# Central_Unit_PCB.net
KiCad netlist of a schematic drawn in EAGLE
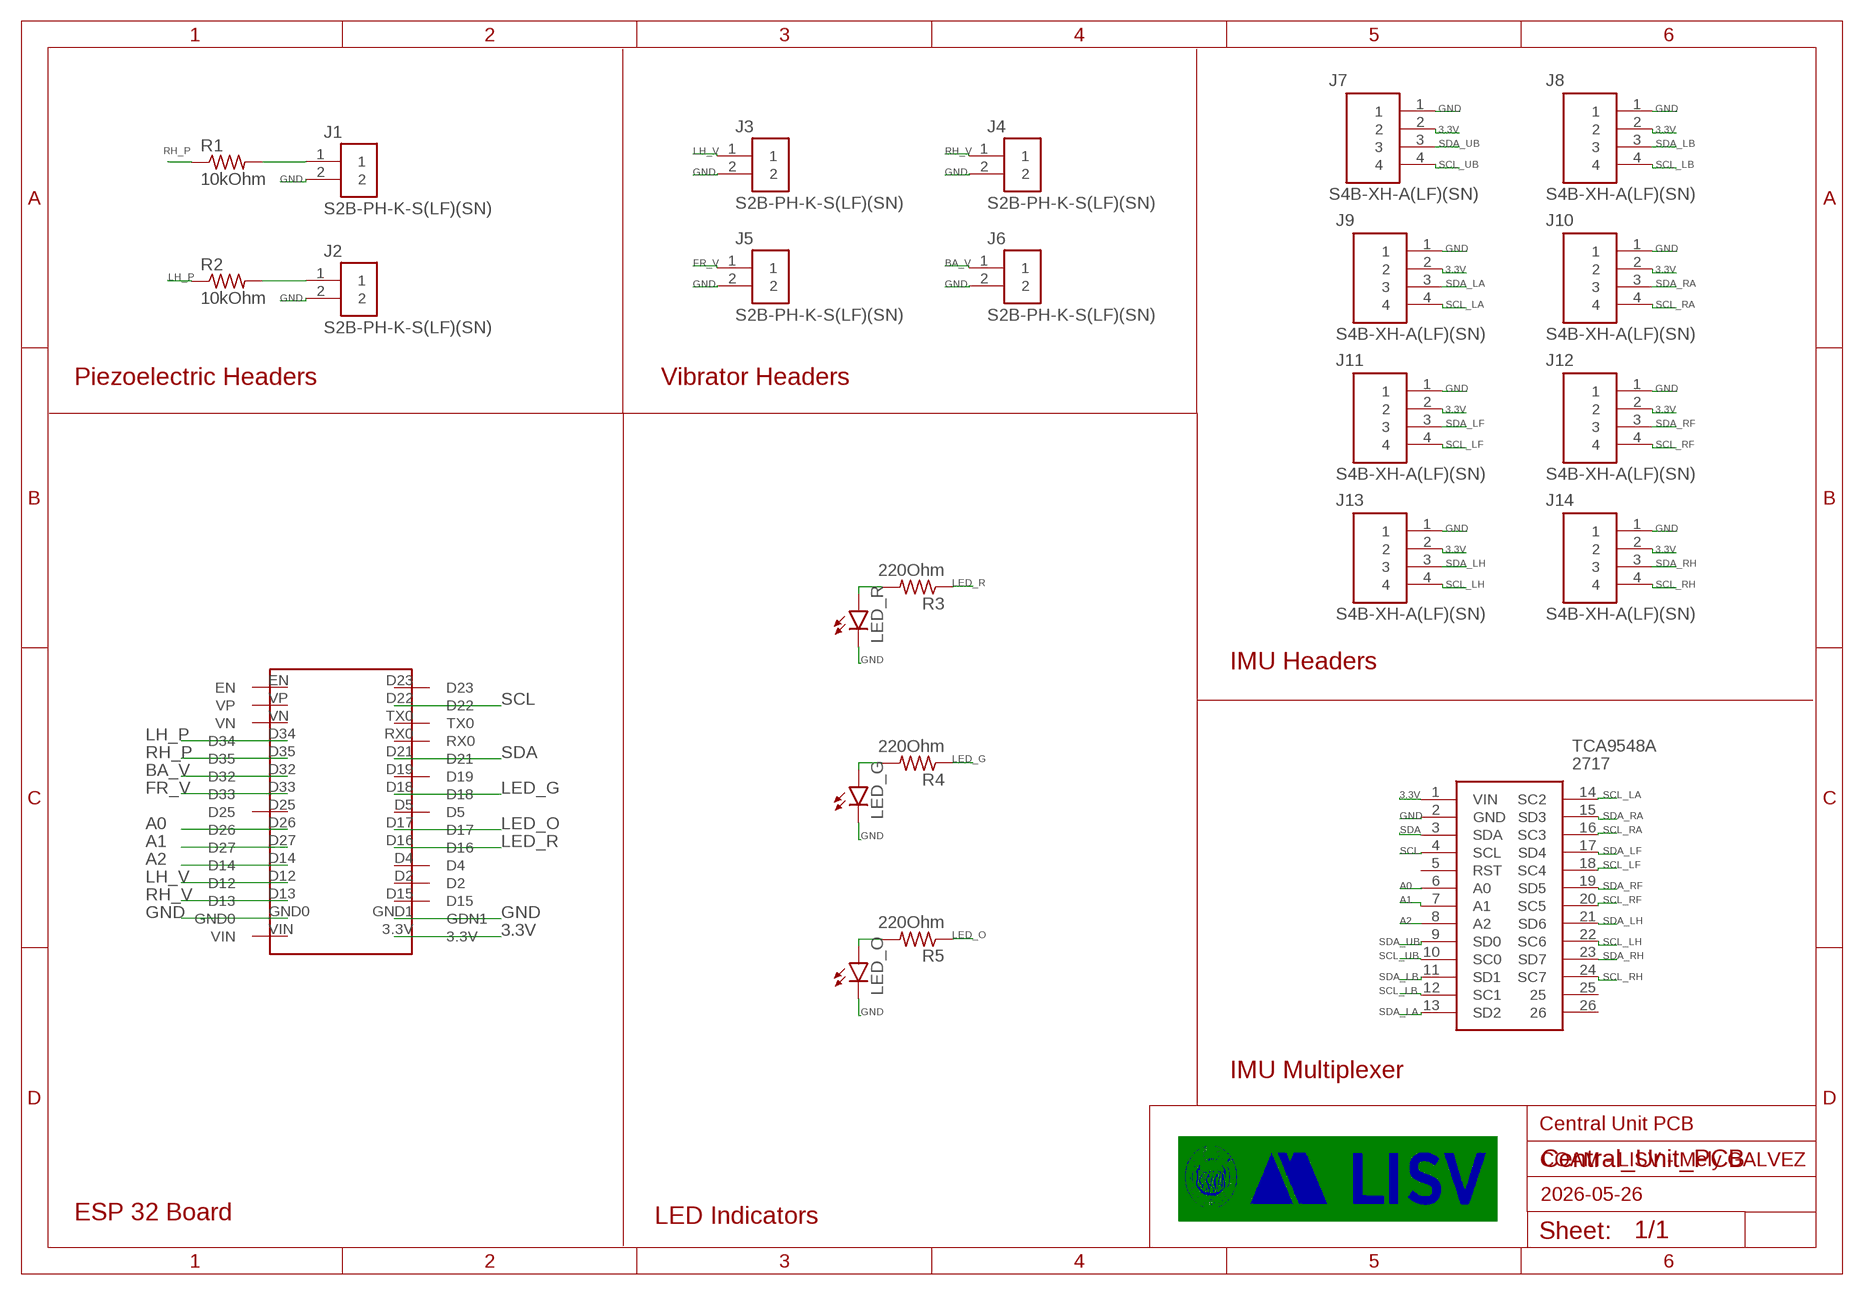
[diagram p0: schematic, sheet 1]

(export (version "E")
  (design (tool "Eeschema 10.0.6"))
  (components
    (comp (ref "J1")
      (value "S2B-PH-K-S(LF)(SN)")
      (footprint "eagle-import:S2B-PH-K-S(LF)(SN)")
      (fields
        (field (name "DIGI_KEY_PART_NUMBER") "455-1719-ND")
        (field (name "MANUFACTURER") "JST Sales America Inc.")
        (field (name "CREATED_BY") "PCBLayout.com")
      )
      (libsource (lib "eagle-import") (part "S2B-PH-K-S(LF)(SN)"))
    )
    (comp (ref "J2")
      (value "S2B-PH-K-S(LF)(SN)")
      (footprint "eagle-import:S2B-PH-K-S(LF)(SN)")
      (fields
        (field (name "DIGI_KEY_PART_NUMBER") "455-1719-ND")
        (field (name "MANUFACTURER") "JST Sales America Inc.")
        (field (name "CREATED_BY") "PCBLayout.com")
      )
      (libsource (lib "eagle-import") (part "S2B-PH-K-S(LF)(SN)"))
    )
    (comp (ref "J3")
      (value "S2B-PH-K-S(LF)(SN)")
      (footprint "eagle-import:S2B-PH-K-S(LF)(SN)")
      (fields
        (field (name "DIGI_KEY_PART_NUMBER") "455-1719-ND")
        (field (name "MANUFACTURER") "JST Sales America Inc.")
        (field (name "CREATED_BY") "PCBLayout.com")
      )
      (libsource (lib "eagle-import") (part "S2B-PH-K-S(LF)(SN)"))
    )
    (comp (ref "J4")
      (value "S2B-PH-K-S(LF)(SN)")
      (footprint "eagle-import:S2B-PH-K-S(LF)(SN)")
      (fields
        (field (name "DIGI_KEY_PART_NUMBER") "455-1719-ND")
        (field (name "MANUFACTURER") "JST Sales America Inc.")
        (field (name "CREATED_BY") "PCBLayout.com")
      )
      (libsource (lib "eagle-import") (part "S2B-PH-K-S(LF)(SN)"))
    )
    (comp (ref "J5")
      (value "S2B-PH-K-S(LF)(SN)")
      (footprint "eagle-import:S2B-PH-K-S(LF)(SN)")
      (fields
        (field (name "DIGI_KEY_PART_NUMBER") "455-1719-ND")
        (field (name "MANUFACTURER") "JST Sales America Inc.")
        (field (name "CREATED_BY") "PCBLayout.com")
      )
      (libsource (lib "eagle-import") (part "S2B-PH-K-S(LF)(SN)"))
    )
    (comp (ref "J6")
      (value "S2B-PH-K-S(LF)(SN)")
      (footprint "eagle-import:S2B-PH-K-S(LF)(SN)")
      (fields
        (field (name "DIGI_KEY_PART_NUMBER") "455-1719-ND")
        (field (name "MANUFACTURER") "JST Sales America Inc.")
        (field (name "CREATED_BY") "PCBLayout.com")
      )
      (libsource (lib "eagle-import") (part "S2B-PH-K-S(LF)(SN)"))
    )
    (comp (ref "J7")
      (value "S4B-XH-A(LF)(SN)")
      (footprint "eagle-import:HDR-04_RA")
      (fields
        (field (name "DIGIKEY_PART_NUMBER") "455-2243-ND")
        (field (name "MANUFACTURER") "JST Sales America Inc.")
        (field (name "CREATED_BY") "PCBLayout.com")
      )
      (libsource (lib "eagle-import") (part "S4B-XH-A(LF)(SN)"))
    )
    (comp (ref "J8")
      (value "S4B-XH-A(LF)(SN)")
      (footprint "eagle-import:HDR-04_RA")
      (fields
        (field (name "DIGIKEY_PART_NUMBER") "455-2243-ND")
        (field (name "MANUFACTURER") "JST Sales America Inc.")
        (field (name "CREATED_BY") "PCBLayout.com")
      )
      (libsource (lib "eagle-import") (part "S4B-XH-A(LF)(SN)"))
    )
    (comp (ref "J9")
      (value "S4B-XH-A(LF)(SN)")
      (footprint "eagle-import:HDR-04_RA")
      (fields
        (field (name "DIGIKEY_PART_NUMBER") "455-2243-ND")
        (field (name "MANUFACTURER") "JST Sales America Inc.")
        (field (name "CREATED_BY") "PCBLayout.com")
      )
      (libsource (lib "eagle-import") (part "S4B-XH-A(LF)(SN)"))
    )
    (comp (ref "J10")
      (value "S4B-XH-A(LF)(SN)")
      (footprint "eagle-import:HDR-04_RA")
      (fields
        (field (name "DIGIKEY_PART_NUMBER") "455-2243-ND")
        (field (name "MANUFACTURER") "JST Sales America Inc.")
        (field (name "CREATED_BY") "PCBLayout.com")
      )
      (libsource (lib "eagle-import") (part "S4B-XH-A(LF)(SN)"))
    )
    (comp (ref "J11")
      (value "S4B-XH-A(LF)(SN)")
      (footprint "eagle-import:HDR-04_RA")
      (fields
        (field (name "DIGIKEY_PART_NUMBER") "455-2243-ND")
        (field (name "MANUFACTURER") "JST Sales America Inc.")
        (field (name "CREATED_BY") "PCBLayout.com")
      )
      (libsource (lib "eagle-import") (part "S4B-XH-A(LF)(SN)"))
    )
    (comp (ref "J12")
      (value "S4B-XH-A(LF)(SN)")
      (footprint "eagle-import:HDR-04_RA")
      (fields
        (field (name "DIGIKEY_PART_NUMBER") "455-2243-ND")
        (field (name "MANUFACTURER") "JST Sales America Inc.")
        (field (name "CREATED_BY") "PCBLayout.com")
      )
      (libsource (lib "eagle-import") (part "S4B-XH-A(LF)(SN)"))
    )
    (comp (ref "J13")
      (value "S4B-XH-A(LF)(SN)")
      (footprint "eagle-import:HDR-04_RA")
      (fields
        (field (name "DIGIKEY_PART_NUMBER") "455-2243-ND")
        (field (name "MANUFACTURER") "JST Sales America Inc.")
        (field (name "CREATED_BY") "PCBLayout.com")
      )
      (libsource (lib "eagle-import") (part "S4B-XH-A(LF)(SN)"))
    )
    (comp (ref "J14")
      (value "S4B-XH-A(LF)(SN)")
      (footprint "eagle-import:HDR-04_RA")
      (fields
        (field (name "DIGIKEY_PART_NUMBER") "455-2243-ND")
        (field (name "MANUFACTURER") "JST Sales America Inc.")
        (field (name "CREATED_BY") "PCBLayout.com")
      )
      (libsource (lib "eagle-import") (part "S4B-XH-A(LF)(SN)"))
    )
    (comp (ref "LED_G")
      (value "LED3MM")
      (footprint "eagle-import:LED3MM")
      (libsource (lib "eagle-import") (part "LED3MM"))
    )
    (comp (ref "LED_O")
      (value "LED3MM")
      (footprint "eagle-import:LED3MM")
      (libsource (lib "eagle-import") (part "LED3MM"))
    )
    (comp (ref "LED_R")
      (value "LED3MM")
      (footprint "eagle-import:LED3MM")
      (libsource (lib "eagle-import") (part "LED3MM"))
    )
    (comp (ref "R1")
      (value "10kOhm")
      (footprint "eagle-import:0207_10")
      (libsource (lib "eagle-import") (part "R-US_0207/10"))
    )
    (comp (ref "R2")
      (value "10kOhm")
      (footprint "eagle-import:0207_10")
      (libsource (lib "eagle-import") (part "R-US_0207/10"))
    )
    (comp (ref "R3")
      (value "220Ohm")
      (footprint "eagle-import:0207_10")
      (libsource (lib "eagle-import") (part "R-US_0207/10"))
    )
    (comp (ref "R4")
      (value "220Ohm")
      (footprint "eagle-import:0207_10")
      (libsource (lib "eagle-import") (part "R-US_0207/10"))
    )
    (comp (ref "R5")
      (value "220Ohm")
      (footprint "eagle-import:0207_10")
      (libsource (lib "eagle-import") (part "R-US_0207/10"))
    )
    (comp (ref "TCA9548A")
      (value "2717")
      (footprint "eagle-import:2717")
      (fields (field (name "MOUSER_PART_NUMBER") "485-2717"))
      (libsource (lib "eagle-import") (part "2717"))
    )
    (comp (ref "U$1")
      (value "ESP32_WROUM32")
      (footprint "eagle-import:ESP32_WROUM32")
      (libsource (lib "eagle-import") (part "ESP32_WROUM32"))
    )
  )
  (nets
    (net (code "1") (name "/3.3V") (class "Default")
      (node (ref "J10") (pin "2") (pinfunction "2_2") (pintype "passive"))
      (node (ref "J11") (pin "2") (pinfunction "2_2") (pintype "passive"))
      (node (ref "J12") (pin "2") (pinfunction "2_2") (pintype "passive"))
      (node (ref "J13") (pin "2") (pinfunction "2_2") (pintype "passive"))
      (node (ref "J14") (pin "2") (pinfunction "2_2") (pintype "passive"))
      (node (ref "J7") (pin "2") (pinfunction "2_2") (pintype "passive"))
      (node (ref "J8") (pin "2") (pinfunction "2_2") (pintype "passive"))
      (node (ref "J9") (pin "2") (pinfunction "2_2") (pintype "passive"))
      (node (ref "TCA9548A") (pin "1") (pinfunction "VIN_1") (pintype "bidirectional"))
      (node (ref "U$1") (pin "3.3V") (pinfunction "3.3V_3.3V") (pintype "output"))
    )
    (net (code "2") (name "/A0") (class "Default")
      (node (ref "TCA9548A") (pin "6") (pinfunction "A0_6") (pintype "bidirectional"))
      (node (ref "U$1") (pin "D26") (pinfunction "D26_D26") (pintype "bidirectional"))
    )
    (net (code "3") (name "/A1") (class "Default")
      (node (ref "TCA9548A") (pin "7") (pinfunction "A1_7") (pintype "bidirectional"))
      (node (ref "U$1") (pin "D27") (pinfunction "D27_D27") (pintype "bidirectional"))
    )
    (net (code "4") (name "/A2") (class "Default")
      (node (ref "TCA9548A") (pin "8") (pinfunction "A2_8") (pintype "bidirectional"))
      (node (ref "U$1") (pin "D14") (pinfunction "D14_D14") (pintype "bidirectional"))
    )
    (net (code "5") (name "/BA_V") (class "Default")
      (node (ref "J6") (pin "1") (pinfunction "1_1") (pintype "passive"))
      (node (ref "U$1") (pin "D32") (pinfunction "D32_D32") (pintype "bidirectional"))
    )
    (net (code "6") (name "/FR_V") (class "Default")
      (node (ref "J5") (pin "1") (pinfunction "1_1") (pintype "passive"))
      (node (ref "U$1") (pin "D33") (pinfunction "D33_D33") (pintype "bidirectional"))
    )
    (net (code "7") (name "/GND") (class "Default")
      (node (ref "J1") (pin "2") (pinfunction "2_2") (pintype "passive"))
      (node (ref "J10") (pin "1") (pinfunction "1_1") (pintype "passive"))
      (node (ref "J11") (pin "1") (pinfunction "1_1") (pintype "passive"))
      (node (ref "J12") (pin "1") (pinfunction "1_1") (pintype "passive"))
      (node (ref "J13") (pin "1") (pinfunction "1_1") (pintype "passive"))
      (node (ref "J14") (pin "1") (pinfunction "1_1") (pintype "passive"))
      (node (ref "J2") (pin "2") (pinfunction "2_2") (pintype "passive"))
      (node (ref "J3") (pin "2") (pinfunction "2_2") (pintype "passive"))
      (node (ref "J4") (pin "2") (pinfunction "2_2") (pintype "passive"))
      (node (ref "J5") (pin "2") (pinfunction "2_2") (pintype "passive"))
      (node (ref "J6") (pin "2") (pinfunction "2_2") (pintype "passive"))
      (node (ref "J7") (pin "1") (pinfunction "1_1") (pintype "passive"))
      (node (ref "J8") (pin "1") (pinfunction "1_1") (pintype "passive"))
      (node (ref "J9") (pin "1") (pinfunction "1_1") (pintype "passive"))
      (node (ref "LED_G") (pin "K") (pinfunction "C_K") (pintype "passive"))
      (node (ref "LED_O") (pin "K") (pinfunction "C_K") (pintype "passive"))
      (node (ref "LED_R") (pin "K") (pinfunction "C_K") (pintype "passive"))
      (node (ref "TCA9548A") (pin "2") (pinfunction "GND_2") (pintype "bidirectional"))
      (node (ref "U$1") (pin "GND0") (pinfunction "GND0_GND0") (pintype "output"))
      (node (ref "U$1") (pin "GND1") (pinfunction "GDN1_GND1") (pintype "output"))
    )
    (net (code "8") (name "/LED_G") (class "Default")
      (node (ref "R4") (pin "1") (pinfunction "1_1") (pintype "passive"))
      (node (ref "U$1") (pin "D18") (pinfunction "D18_D18") (pintype "bidirectional"))
    )
    (net (code "9") (name "/LED_O") (class "Default")
      (node (ref "R5") (pin "1") (pinfunction "1_1") (pintype "passive"))
      (node (ref "U$1") (pin "D17") (pinfunction "D17_D17") (pintype "bidirectional"))
    )
    (net (code "10") (name "/LED_R") (class "Default")
      (node (ref "R3") (pin "1") (pinfunction "1_1") (pintype "passive"))
      (node (ref "U$1") (pin "D16") (pinfunction "D16_D16") (pintype "bidirectional"))
    )
    (net (code "11") (name "/LH_P") (class "Default")
      (node (ref "R2") (pin "1") (pinfunction "1_1") (pintype "passive"))
      (node (ref "U$1") (pin "D34") (pinfunction "D34_D34") (pintype "bidirectional"))
    )
    (net (code "12") (name "/LH_V") (class "Default")
      (node (ref "J3") (pin "1") (pinfunction "1_1") (pintype "passive"))
      (node (ref "U$1") (pin "D12") (pinfunction "D12_D12") (pintype "bidirectional"))
    )
    (net (code "13") (name "/RH_P") (class "Default")
      (node (ref "R1") (pin "1") (pinfunction "1_1") (pintype "passive"))
      (node (ref "U$1") (pin "D35") (pinfunction "D35_D35") (pintype "bidirectional"))
    )
    (net (code "14") (name "/RH_V") (class "Default")
      (node (ref "J4") (pin "1") (pinfunction "1_1") (pintype "passive"))
      (node (ref "U$1") (pin "D13") (pinfunction "D13_D13") (pintype "bidirectional"))
    )
    (net (code "15") (name "/SCL") (class "Default")
      (node (ref "TCA9548A") (pin "4") (pinfunction "SCL_4") (pintype "bidirectional"))
      (node (ref "U$1") (pin "D22") (pinfunction "D22_D22") (pintype "bidirectional"))
    )
    (net (code "16") (name "/SCL_LA") (class "Default")
      (node (ref "J9") (pin "4") (pinfunction "4_4") (pintype "passive"))
      (node (ref "TCA9548A") (pin "14") (pinfunction "SC2_14") (pintype "bidirectional"))
    )
    (net (code "17") (name "/SCL_LB") (class "Default")
      (node (ref "J8") (pin "4") (pinfunction "4_4") (pintype "passive"))
      (node (ref "TCA9548A") (pin "12") (pinfunction "SC1_12") (pintype "bidirectional"))
    )
    (net (code "18") (name "/SCL_LF") (class "Default")
      (node (ref "J11") (pin "4") (pinfunction "4_4") (pintype "passive"))
      (node (ref "TCA9548A") (pin "18") (pinfunction "SC4_18") (pintype "bidirectional"))
    )
    (net (code "19") (name "/SCL_LH") (class "Default")
      (node (ref "J13") (pin "4") (pinfunction "4_4") (pintype "passive"))
      (node (ref "TCA9548A") (pin "22") (pinfunction "SC6_22") (pintype "bidirectional"))
    )
    (net (code "20") (name "/SCL_RA") (class "Default")
      (node (ref "J10") (pin "4") (pinfunction "4_4") (pintype "passive"))
      (node (ref "TCA9548A") (pin "16") (pinfunction "SC3_16") (pintype "bidirectional"))
    )
    (net (code "21") (name "/SCL_RF") (class "Default")
      (node (ref "J12") (pin "4") (pinfunction "4_4") (pintype "passive"))
      (node (ref "TCA9548A") (pin "20") (pinfunction "SC5_20") (pintype "bidirectional"))
    )
    (net (code "22") (name "/SCL_RH") (class "Default")
      (node (ref "J14") (pin "4") (pinfunction "4_4") (pintype "passive"))
      (node (ref "TCA9548A") (pin "24") (pinfunction "SC7_24") (pintype "bidirectional"))
    )
    (net (code "23") (name "/SCL_UB") (class "Default")
      (node (ref "J7") (pin "4") (pinfunction "4_4") (pintype "passive"))
      (node (ref "TCA9548A") (pin "10") (pinfunction "SC0_10") (pintype "bidirectional"))
    )
    (net (code "24") (name "/SDA") (class "Default")
      (node (ref "TCA9548A") (pin "3") (pinfunction "SDA_3") (pintype "bidirectional"))
      (node (ref "U$1") (pin "D21") (pinfunction "D21_D21") (pintype "bidirectional"))
    )
    (net (code "25") (name "/SDA_LA") (class "Default")
      (node (ref "J9") (pin "3") (pinfunction "3_3") (pintype "passive"))
      (node (ref "TCA9548A") (pin "13") (pinfunction "SD2_13") (pintype "bidirectional"))
    )
    (net (code "26") (name "/SDA_LB") (class "Default")
      (node (ref "J8") (pin "3") (pinfunction "3_3") (pintype "passive"))
      (node (ref "TCA9548A") (pin "11") (pinfunction "SD1_11") (pintype "bidirectional"))
    )
    (net (code "27") (name "/SDA_LF") (class "Default")
      (node (ref "J11") (pin "3") (pinfunction "3_3") (pintype "passive"))
      (node (ref "TCA9548A") (pin "17") (pinfunction "SD4_17") (pintype "bidirectional"))
    )
    (net (code "28") (name "/SDA_LH") (class "Default")
      (node (ref "J13") (pin "3") (pinfunction "3_3") (pintype "passive"))
      (node (ref "TCA9548A") (pin "21") (pinfunction "SD6_21") (pintype "bidirectional"))
    )
    (net (code "29") (name "/SDA_RA") (class "Default")
      (node (ref "J10") (pin "3") (pinfunction "3_3") (pintype "passive"))
      (node (ref "TCA9548A") (pin "15") (pinfunction "SD3_15") (pintype "bidirectional"))
    )
    (net (code "30") (name "/SDA_RF") (class "Default")
      (node (ref "J12") (pin "3") (pinfunction "3_3") (pintype "passive"))
      (node (ref "TCA9548A") (pin "19") (pinfunction "SD5_19") (pintype "bidirectional"))
    )
    (net (code "31") (name "/SDA_RH") (class "Default")
      (node (ref "J14") (pin "3") (pinfunction "3_3") (pintype "passive"))
      (node (ref "TCA9548A") (pin "23") (pinfunction "SD7_23") (pintype "bidirectional"))
    )
    (net (code "32") (name "/SDA_UB") (class "Default")
      (node (ref "J7") (pin "3") (pinfunction "3_3") (pintype "passive"))
      (node (ref "TCA9548A") (pin "9") (pinfunction "SD0_9") (pintype "bidirectional"))
    )
    (net (code "33") (name "Net-(J1-Pad1)") (class "Default")
      (node (ref "J1") (pin "1") (pinfunction "1_1") (pintype "passive"))
      (node (ref "R1") (pin "2") (pinfunction "2_2") (pintype "passive"))
    )
    (net (code "34") (name "Net-(J2-Pad1)") (class "Default")
      (node (ref "J2") (pin "1") (pinfunction "1_1") (pintype "passive"))
      (node (ref "R2") (pin "2") (pinfunction "2_2") (pintype "passive"))
    )
    (net (code "35") (name "Net-(LED_G-PadA)") (class "Default")
      (node (ref "LED_G") (pin "A") (pinfunction "A_A") (pintype "passive"))
      (node (ref "R4") (pin "2") (pinfunction "2_2") (pintype "passive"))
    )
    (net (code "36") (name "Net-(LED_O-PadA)") (class "Default")
      (node (ref "LED_O") (pin "A") (pinfunction "A_A") (pintype "passive"))
      (node (ref "R5") (pin "2") (pinfunction "2_2") (pintype "passive"))
    )
    (net (code "37") (name "Net-(LED_R-PadA)") (class "Default")
      (node (ref "LED_R") (pin "A") (pinfunction "A_A") (pintype "passive"))
      (node (ref "R3") (pin "2") (pinfunction "2_2") (pintype "passive"))
    )
    (net (code "38") (name "unconnected-(TCA9548A-Pad25)") (class "Default")
      (node (ref "TCA9548A") (pin "25") (pinfunction "25_25") (pintype "bidirectional"))
    )
    (net (code "39") (name "unconnected-(TCA9548A-Pad26)") (class "Default")
      (node (ref "TCA9548A") (pin "26") (pinfunction "26_26") (pintype "bidirectional"))
    )
    (net (code "40") (name "unconnected-(TCA9548A-RST-Pad5)") (class "Default")
      (node (ref "TCA9548A") (pin "5") (pinfunction "RST_5") (pintype "bidirectional"))
    )
    (net (code "41") (name "unconnected-(U$1-PadD2)") (class "Default")
      (node (ref "U$1") (pin "D2") (pinfunction "D2_D2") (pintype "bidirectional"))
    )
    (net (code "42") (name "unconnected-(U$1-PadD4)") (class "Default")
      (node (ref "U$1") (pin "D4") (pinfunction "D4_D4") (pintype "bidirectional"))
    )
    (net (code "43") (name "unconnected-(U$1-PadD5)") (class "Default")
      (node (ref "U$1") (pin "D5") (pinfunction "D5_D5") (pintype "bidirectional"))
    )
    (net (code "44") (name "unconnected-(U$1-PadD15)") (class "Default")
      (node (ref "U$1") (pin "D15") (pinfunction "D15_D15") (pintype "bidirectional"))
    )
    (net (code "45") (name "unconnected-(U$1-PadD19)") (class "Default")
      (node (ref "U$1") (pin "D19") (pinfunction "D19_D19") (pintype "bidirectional"))
    )
    (net (code "46") (name "unconnected-(U$1-PadD23)") (class "Default")
      (node (ref "U$1") (pin "D23") (pinfunction "D23_D23") (pintype "bidirectional"))
    )
    (net (code "47") (name "unconnected-(U$1-PadD25)") (class "Default")
      (node (ref "U$1") (pin "D25") (pinfunction "D25_D25") (pintype "bidirectional"))
    )
    (net (code "48") (name "unconnected-(U$1-PadEN)") (class "Default")
      (node (ref "U$1") (pin "EN") (pinfunction "EN_EN") (pintype "bidirectional"))
    )
    (net (code "49") (name "unconnected-(U$1-PadRX0)") (class "Default")
      (node (ref "U$1") (pin "RX0") (pinfunction "RX0_RX0") (pintype "bidirectional"))
    )
    (net (code "50") (name "unconnected-(U$1-PadTX0)") (class "Default")
      (node (ref "U$1") (pin "TX0") (pinfunction "TX0_TX0") (pintype "bidirectional"))
    )
    (net (code "51") (name "unconnected-(U$1-PadVIN)") (class "Default")
      (node (ref "U$1") (pin "VIN") (pinfunction "VIN_VIN") (pintype "output"))
    )
    (net (code "52") (name "unconnected-(U$1-PadVN)") (class "Default")
      (node (ref "U$1") (pin "VN") (pinfunction "VN_VN") (pintype "bidirectional"))
    )
    (net (code "53") (name "unconnected-(U$1-PadVP)") (class "Default")
      (node (ref "U$1") (pin "VP") (pinfunction "VP_VP") (pintype "bidirectional"))
    )
  )
)
